# matrix-only.net
KiCad netlist of a schematic drawn in EAGLE
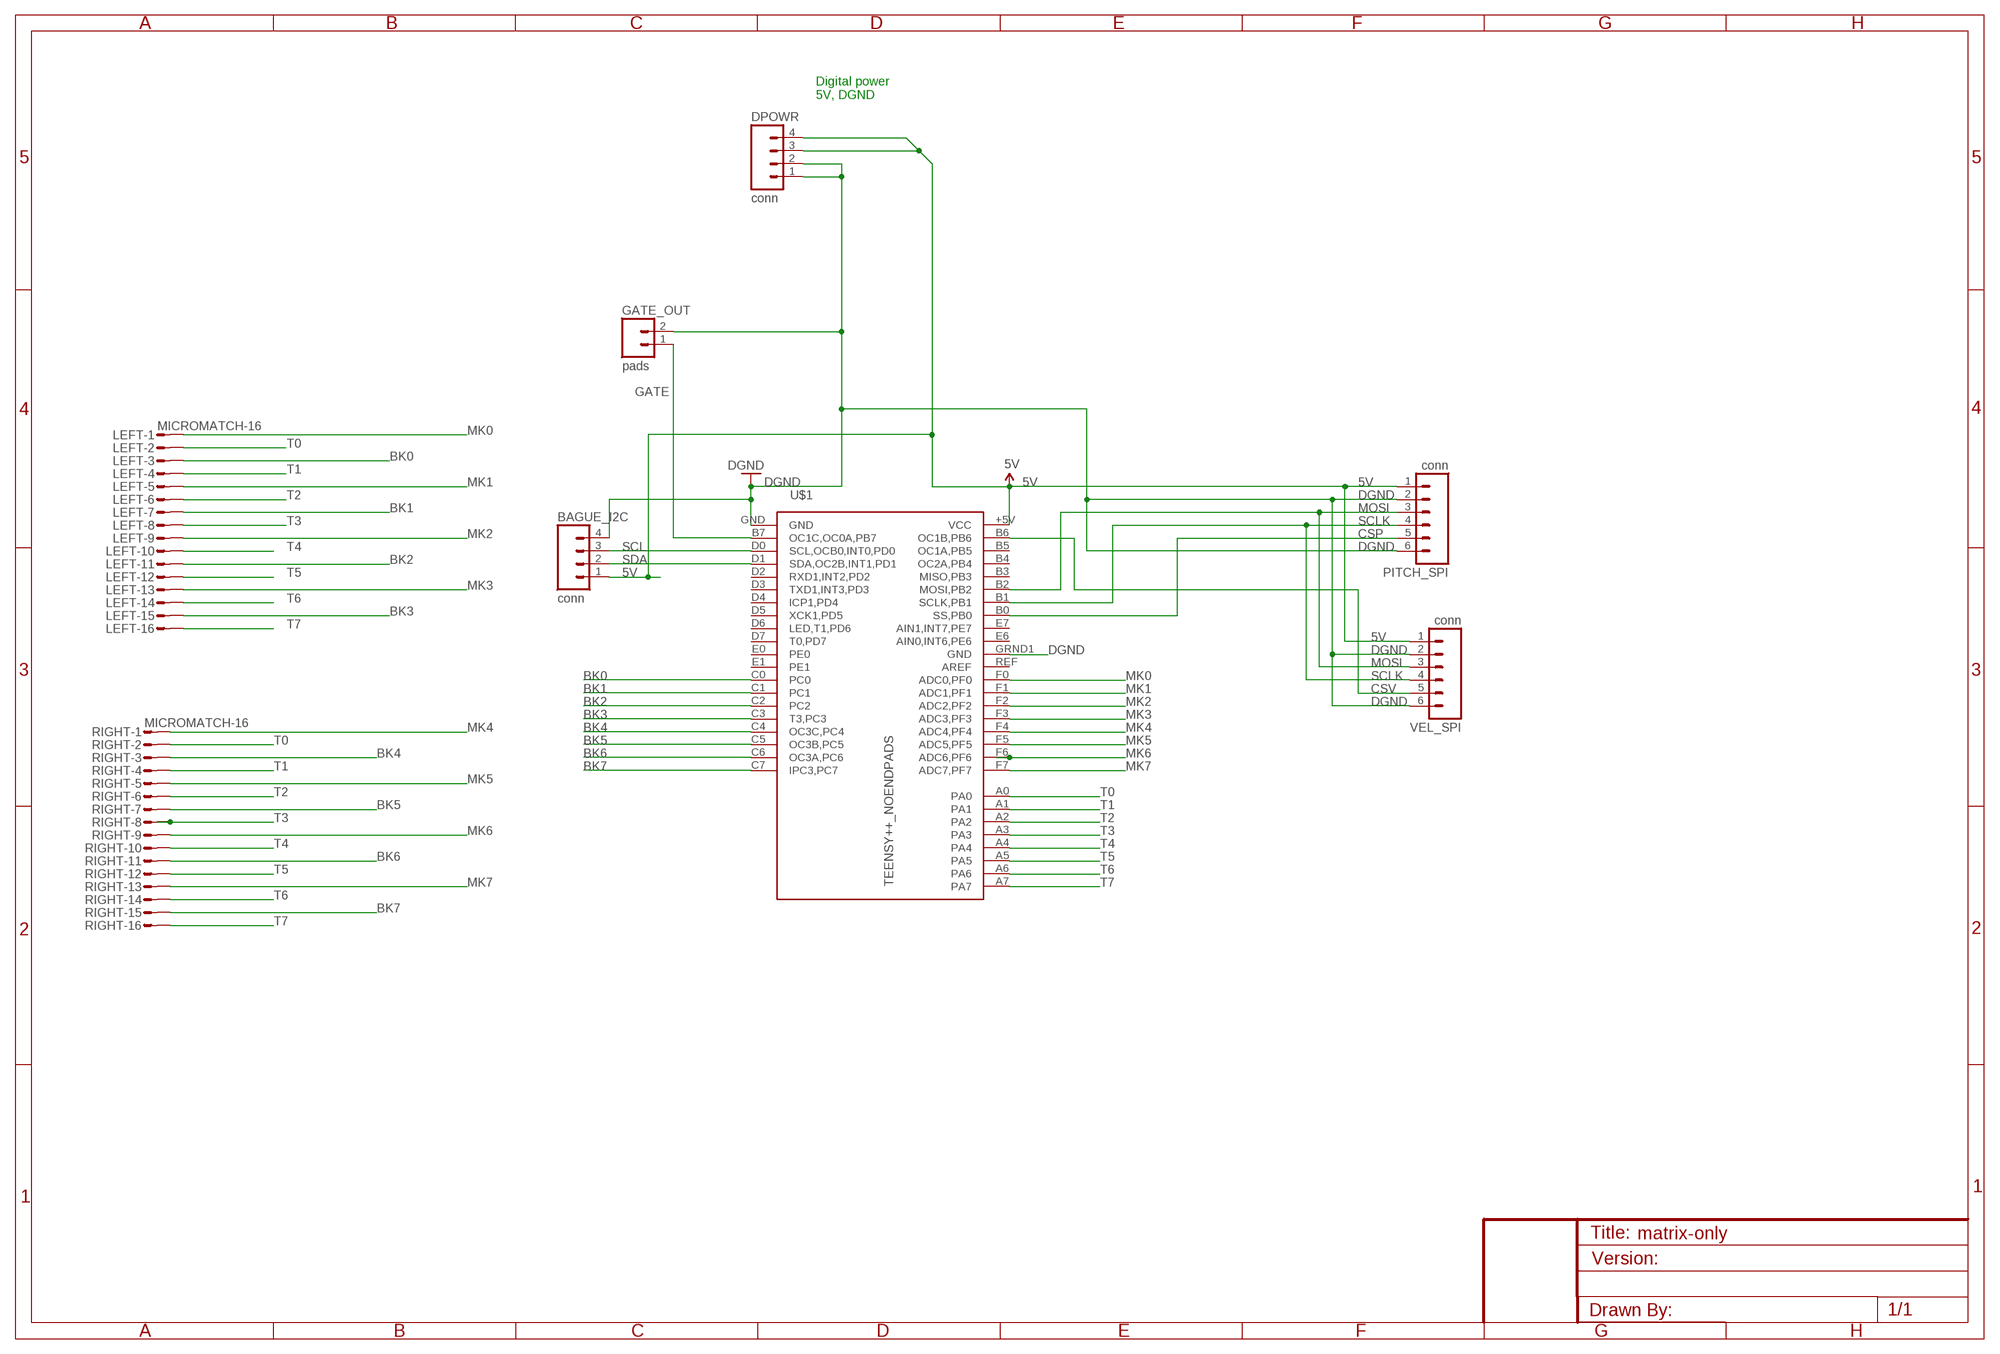
[diagram p0: schematic, sheet 1]

(export (version "E")
  (design (tool "Eeschema 10.0.6"))
  (components
    (comp (ref "BAGUE_I2C")
      (value "conn")
      (footprint "eagle-import:1X04_LOCK")
      (libsource (lib "eagle-import") (part "M04LOCK"))
    )
    (comp (ref "DPOWR")
      (value "conn")
      (footprint "eagle-import:1X04")
      (libsource (lib "eagle-import") (part "M04PTH"))
    )
    (comp (ref "GATE_OUT")
      (value "pads")
      (footprint "eagle-import:1X02_LONGPADS")
      (libsource (lib "eagle-import") (part "M02PTH3"))
    )
    (comp (ref "LEFT")
      (value "MICROMATCH-16")
      (footprint "eagle-import:MICROMATCH-16")
      (fields (field (name "MF") "FARNELL") (field (name "MPN") "8-215464-6"))
      (libsource (lib "eagle-import") (part "MICROMATCH-16"))
    )
    (comp (ref "PITCH_SPI")
      (value "conn")
      (footprint "eagle-import:1X06")
      (libsource (lib "eagle-import") (part "M06SIP"))
    )
    (comp (ref "RIGHT")
      (value "MICROMATCH-16")
      (footprint "eagle-import:MICROMATCH-16")
      (fields (field (name "MF") "FARNELL") (field (name "MPN") "8-215464-6"))
      (libsource (lib "eagle-import") (part "MICROMATCH-16"))
    )
    (comp (ref "U$1")
      (value "TEENSY++_NOENDPADS")
      (footprint "eagle-import:TEENSY++")
      (libsource (lib "eagle-import") (part "TEENSY++_NOENDPADS"))
    )
    (comp (ref "VEL_SPI")
      (value "conn")
      (footprint "eagle-import:1X06")
      (libsource (lib "eagle-import") (part "M06SIP"))
    )
  )
  (nets
    (net (code "1") (name "/BK0") (class "Default")
      (node (ref "LEFT") (pin "3") (pinfunction "S_3") (pintype "passive"))
      (node (ref "U$1") (pin "C0") (pinfunction "PC0_C0") (pintype "bidirectional"))
    )
    (net (code "2") (name "/BK1") (class "Default")
      (node (ref "LEFT") (pin "7") (pinfunction "S_7") (pintype "passive"))
      (node (ref "U$1") (pin "C1") (pinfunction "PC1_C1") (pintype "bidirectional"))
    )
    (net (code "3") (name "/BK2") (class "Default")
      (node (ref "LEFT") (pin "11") (pinfunction "S_11") (pintype "passive"))
      (node (ref "U$1") (pin "C2") (pinfunction "PC2_C2") (pintype "bidirectional"))
    )
    (net (code "4") (name "/BK3") (class "Default")
      (node (ref "LEFT") (pin "15") (pinfunction "S_15") (pintype "passive"))
      (node (ref "U$1") (pin "C3") (pinfunction "T3,PC3_C3") (pintype "bidirectional"))
    )
    (net (code "5") (name "/BK4") (class "Default")
      (node (ref "RIGHT") (pin "3") (pinfunction "S_3") (pintype "passive"))
      (node (ref "U$1") (pin "C4") (pinfunction "OC3C,PC4_C4") (pintype "bidirectional"))
    )
    (net (code "6") (name "/BK5") (class "Default")
      (node (ref "RIGHT") (pin "7") (pinfunction "S_7") (pintype "passive"))
      (node (ref "U$1") (pin "C5") (pinfunction "OC3B,PC5_C5") (pintype "bidirectional"))
    )
    (net (code "7") (name "/BK6") (class "Default")
      (node (ref "RIGHT") (pin "11") (pinfunction "S_11") (pintype "passive"))
      (node (ref "U$1") (pin "C6") (pinfunction "OC3A,PC6_C6") (pintype "bidirectional"))
    )
    (net (code "8") (name "/BK7") (class "Default")
      (node (ref "RIGHT") (pin "15") (pinfunction "S_15") (pintype "passive"))
      (node (ref "U$1") (pin "C7") (pinfunction "IPC3,PC7_C7") (pintype "bidirectional"))
    )
    (net (code "9") (name "/CSP") (class "Default")
      (node (ref "PITCH_SPI") (pin "5") (pinfunction "5_5") (pintype "passive"))
      (node (ref "U$1") (pin "B0") (pinfunction "SS,PB0_B0") (pintype "bidirectional"))
    )
    (net (code "10") (name "/CSV") (class "Default")
      (node (ref "U$1") (pin "B6") (pinfunction "OC1B,PB6_B6") (pintype "bidirectional"))
      (node (ref "VEL_SPI") (pin "5") (pinfunction "5_5") (pintype "passive"))
    )
    (net (code "11") (name "/GATE") (class "Default")
      (node (ref "GATE_OUT") (pin "1") (pinfunction "1_1") (pintype "passive"))
      (node (ref "U$1") (pin "B7") (pinfunction "OC1C,OC0A,PB7_B7") (pintype "bidirectional"))
    )
    (net (code "12") (name "/MK0") (class "Default")
      (node (ref "LEFT") (pin "1") (pinfunction "S_1") (pintype "passive"))
      (node (ref "U$1") (pin "F0") (pinfunction "ADC0,PF0_F0") (pintype "bidirectional"))
    )
    (net (code "13") (name "/MK1") (class "Default")
      (node (ref "LEFT") (pin "5") (pinfunction "S_5") (pintype "passive"))
      (node (ref "U$1") (pin "F1") (pinfunction "ADC1,PF1_F1") (pintype "bidirectional"))
    )
    (net (code "14") (name "/MK2") (class "Default")
      (node (ref "LEFT") (pin "9") (pinfunction "S_9") (pintype "passive"))
      (node (ref "U$1") (pin "F2") (pinfunction "ADC2,PF2_F2") (pintype "bidirectional"))
    )
    (net (code "15") (name "/MK3") (class "Default")
      (node (ref "LEFT") (pin "13") (pinfunction "S_13") (pintype "passive"))
      (node (ref "U$1") (pin "F3") (pinfunction "ADC3,PF3_F3") (pintype "bidirectional"))
    )
    (net (code "16") (name "/MK4") (class "Default")
      (node (ref "RIGHT") (pin "1") (pinfunction "S_1") (pintype "passive"))
      (node (ref "U$1") (pin "F4") (pinfunction "ADC4,PF4_F4") (pintype "bidirectional"))
    )
    (net (code "17") (name "/MK5") (class "Default")
      (node (ref "RIGHT") (pin "5") (pinfunction "S_5") (pintype "passive"))
      (node (ref "U$1") (pin "F5") (pinfunction "ADC5,PF5_F5") (pintype "bidirectional"))
    )
    (net (code "18") (name "/MK6") (class "Default")
      (node (ref "RIGHT") (pin "9") (pinfunction "S_9") (pintype "passive"))
      (node (ref "U$1") (pin "F6") (pinfunction "ADC6,PF6_F6") (pintype "bidirectional"))
    )
    (net (code "19") (name "/MK7") (class "Default")
      (node (ref "RIGHT") (pin "13") (pinfunction "S_13") (pintype "passive"))
      (node (ref "U$1") (pin "F7") (pinfunction "ADC7,PF7_F7") (pintype "bidirectional"))
    )
    (net (code "20") (name "/MOSI") (class "Default")
      (node (ref "PITCH_SPI") (pin "3") (pinfunction "3_3") (pintype "passive"))
      (node (ref "U$1") (pin "B2") (pinfunction "MOSI,PB2_B2") (pintype "bidirectional"))
      (node (ref "VEL_SPI") (pin "3") (pinfunction "3_3") (pintype "passive"))
    )
    (net (code "21") (name "/SCL") (class "Default")
      (node (ref "BAGUE_I2C") (pin "3") (pinfunction "3_3") (pintype "passive"))
      (node (ref "U$1") (pin "D0") (pinfunction "SCL,OCB0,INT0,PD0_D0") (pintype "bidirectional"))
    )
    (net (code "22") (name "/SCLK") (class "Default")
      (node (ref "PITCH_SPI") (pin "4") (pinfunction "4_4") (pintype "passive"))
      (node (ref "U$1") (pin "B1") (pinfunction "SCLK,PB1_B1") (pintype "bidirectional"))
      (node (ref "VEL_SPI") (pin "4") (pinfunction "4_4") (pintype "passive"))
    )
    (net (code "23") (name "/SDA") (class "Default")
      (node (ref "BAGUE_I2C") (pin "2") (pinfunction "2_2") (pintype "passive"))
      (node (ref "U$1") (pin "D1") (pinfunction "SDA,OC2B,INT1,PD1_D1") (pintype "bidirectional"))
    )
    (net (code "24") (name "/T0") (class "Default")
      (node (ref "LEFT") (pin "2") (pinfunction "S_2") (pintype "passive"))
      (node (ref "RIGHT") (pin "2") (pinfunction "S_2") (pintype "passive"))
      (node (ref "U$1") (pin "A0") (pinfunction "PA0_A0") (pintype "bidirectional"))
    )
    (net (code "25") (name "/T1") (class "Default")
      (node (ref "LEFT") (pin "4") (pinfunction "S_4") (pintype "passive"))
      (node (ref "RIGHT") (pin "4") (pinfunction "S_4") (pintype "passive"))
      (node (ref "U$1") (pin "A1") (pinfunction "PA1_A1") (pintype "bidirectional"))
    )
    (net (code "26") (name "/T2") (class "Default")
      (node (ref "LEFT") (pin "6") (pinfunction "S_6") (pintype "passive"))
      (node (ref "RIGHT") (pin "6") (pinfunction "S_6") (pintype "passive"))
      (node (ref "U$1") (pin "A2") (pinfunction "PA2_A2") (pintype "bidirectional"))
    )
    (net (code "27") (name "/T3") (class "Default")
      (node (ref "LEFT") (pin "8") (pinfunction "S_8") (pintype "passive"))
      (node (ref "RIGHT") (pin "8") (pinfunction "S_8") (pintype "passive"))
      (node (ref "U$1") (pin "A3") (pinfunction "PA3_A3") (pintype "bidirectional"))
    )
    (net (code "28") (name "/T4") (class "Default")
      (node (ref "LEFT") (pin "10") (pinfunction "S_10") (pintype "passive"))
      (node (ref "RIGHT") (pin "10") (pinfunction "S_10") (pintype "passive"))
      (node (ref "U$1") (pin "A4") (pinfunction "PA4_A4") (pintype "bidirectional"))
    )
    (net (code "29") (name "/T5") (class "Default")
      (node (ref "LEFT") (pin "12") (pinfunction "S_12") (pintype "passive"))
      (node (ref "RIGHT") (pin "12") (pinfunction "S_12") (pintype "passive"))
      (node (ref "U$1") (pin "A5") (pinfunction "PA5_A5") (pintype "bidirectional"))
    )
    (net (code "30") (name "/T6") (class "Default")
      (node (ref "LEFT") (pin "14") (pinfunction "S_14") (pintype "passive"))
      (node (ref "RIGHT") (pin "14") (pinfunction "S_14") (pintype "passive"))
      (node (ref "U$1") (pin "A6") (pinfunction "PA6_A6") (pintype "bidirectional"))
    )
    (net (code "31") (name "/T7") (class "Default")
      (node (ref "LEFT") (pin "16") (pinfunction "S_16") (pintype "passive"))
      (node (ref "RIGHT") (pin "16") (pinfunction "S_16") (pintype "passive"))
      (node (ref "U$1") (pin "A7") (pinfunction "PA7_A7") (pintype "bidirectional"))
    )
    (net (code "32") (name "5V") (class "Default")
      (node (ref "BAGUE_I2C") (pin "1") (pinfunction "1_1") (pintype "passive"))
      (node (ref "DPOWR") (pin "3") (pinfunction "3_3") (pintype "passive"))
      (node (ref "DPOWR") (pin "4") (pinfunction "4_4") (pintype "passive"))
      (node (ref "PITCH_SPI") (pin "1") (pinfunction "1_1") (pintype "passive"))
      (node (ref "U$1") (pin "+5V") (pinfunction "VCC_+5V") (pintype "power_in"))
      (node (ref "VEL_SPI") (pin "1") (pinfunction "1_1") (pintype "passive"))
    )
    (net (code "33") (name "DGND") (class "Default")
      (node (ref "BAGUE_I2C") (pin "4") (pinfunction "4_4") (pintype "passive"))
      (node (ref "DPOWR") (pin "1") (pinfunction "1_1") (pintype "passive"))
      (node (ref "DPOWR") (pin "2") (pinfunction "2_2") (pintype "passive"))
      (node (ref "GATE_OUT") (pin "2") (pinfunction "2_2") (pintype "passive"))
      (node (ref "PITCH_SPI") (pin "2") (pinfunction "2_2") (pintype "passive"))
      (node (ref "PITCH_SPI") (pin "6") (pinfunction "6_6") (pintype "passive"))
      (node (ref "U$1") (pin "GND") (pinfunction "GND_GND") (pintype "power_in"))
      (node (ref "U$1") (pin "GRND1") (pinfunction "GND_GRND1") (pintype "power_in"))
      (node (ref "VEL_SPI") (pin "2") (pinfunction "2_2") (pintype "passive"))
      (node (ref "VEL_SPI") (pin "6") (pinfunction "6_6") (pintype "passive"))
    )
    (net (code "34") (name "unconnected-(U$1-AIN0,INT6,PE6-PadE6)") (class "Default")
      (node (ref "U$1") (pin "E6") (pinfunction "AIN0,INT6,PE6_E6") (pintype "bidirectional"))
    )
    (net (code "35") (name "unconnected-(U$1-AIN1,INT7,PE7-PadE7)") (class "Default")
      (node (ref "U$1") (pin "E7") (pinfunction "AIN1,INT7,PE7_E7") (pintype "bidirectional"))
    )
    (net (code "36") (name "unconnected-(U$1-AREF-PadREF)") (class "Default")
      (node (ref "U$1") (pin "REF") (pinfunction "AREF_REF") (pintype "input"))
    )
    (net (code "37") (name "unconnected-(U$1-ICP1,PD4-PadD4)") (class "Default")
      (node (ref "U$1") (pin "D4") (pinfunction "ICP1,PD4_D4") (pintype "bidirectional"))
    )
    (net (code "38") (name "unconnected-(U$1-LED,T1,PD6-PadD6)") (class "Default")
      (node (ref "U$1") (pin "D6") (pinfunction "LED,T1,PD6_D6") (pintype "bidirectional"))
    )
    (net (code "39") (name "unconnected-(U$1-MISO,PB3-PadB3)") (class "Default")
      (node (ref "U$1") (pin "B3") (pinfunction "MISO,PB3_B3") (pintype "bidirectional"))
    )
    (net (code "40") (name "unconnected-(U$1-OC1A,PB5-PadB5)") (class "Default")
      (node (ref "U$1") (pin "B5") (pinfunction "OC1A,PB5_B5") (pintype "bidirectional"))
    )
    (net (code "41") (name "unconnected-(U$1-OC2A,PB4-PadB4)") (class "Default")
      (node (ref "U$1") (pin "B4") (pinfunction "OC2A,PB4_B4") (pintype "bidirectional"))
    )
    (net (code "42") (name "unconnected-(U$1-PE0-PadE0)") (class "Default")
      (node (ref "U$1") (pin "E0") (pinfunction "PE0_E0") (pintype "bidirectional"))
    )
    (net (code "43") (name "unconnected-(U$1-PE1-PadE1)") (class "Default")
      (node (ref "U$1") (pin "E1") (pinfunction "PE1_E1") (pintype "bidirectional"))
    )
    (net (code "44") (name "unconnected-(U$1-RXD1,INT2,PD2-PadD2)") (class "Default")
      (node (ref "U$1") (pin "D2") (pinfunction "RXD1,INT2,PD2_D2") (pintype "bidirectional"))
    )
    (net (code "45") (name "unconnected-(U$1-T0,PD7-PadD7)") (class "Default")
      (node (ref "U$1") (pin "D7") (pinfunction "T0,PD7_D7") (pintype "bidirectional"))
    )
    (net (code "46") (name "unconnected-(U$1-TXD1,INT3,PD3-PadD3)") (class "Default")
      (node (ref "U$1") (pin "D3") (pinfunction "TXD1,INT3,PD3_D3") (pintype "bidirectional"))
    )
    (net (code "47") (name "unconnected-(U$1-XCK1,PD5-PadD5)") (class "Default")
      (node (ref "U$1") (pin "D5") (pinfunction "XCK1,PD5_D5") (pintype "bidirectional"))
    )
  )
)
